# CAN-I2C.net
KiCad netlist of a schematic drawn in EAGLE
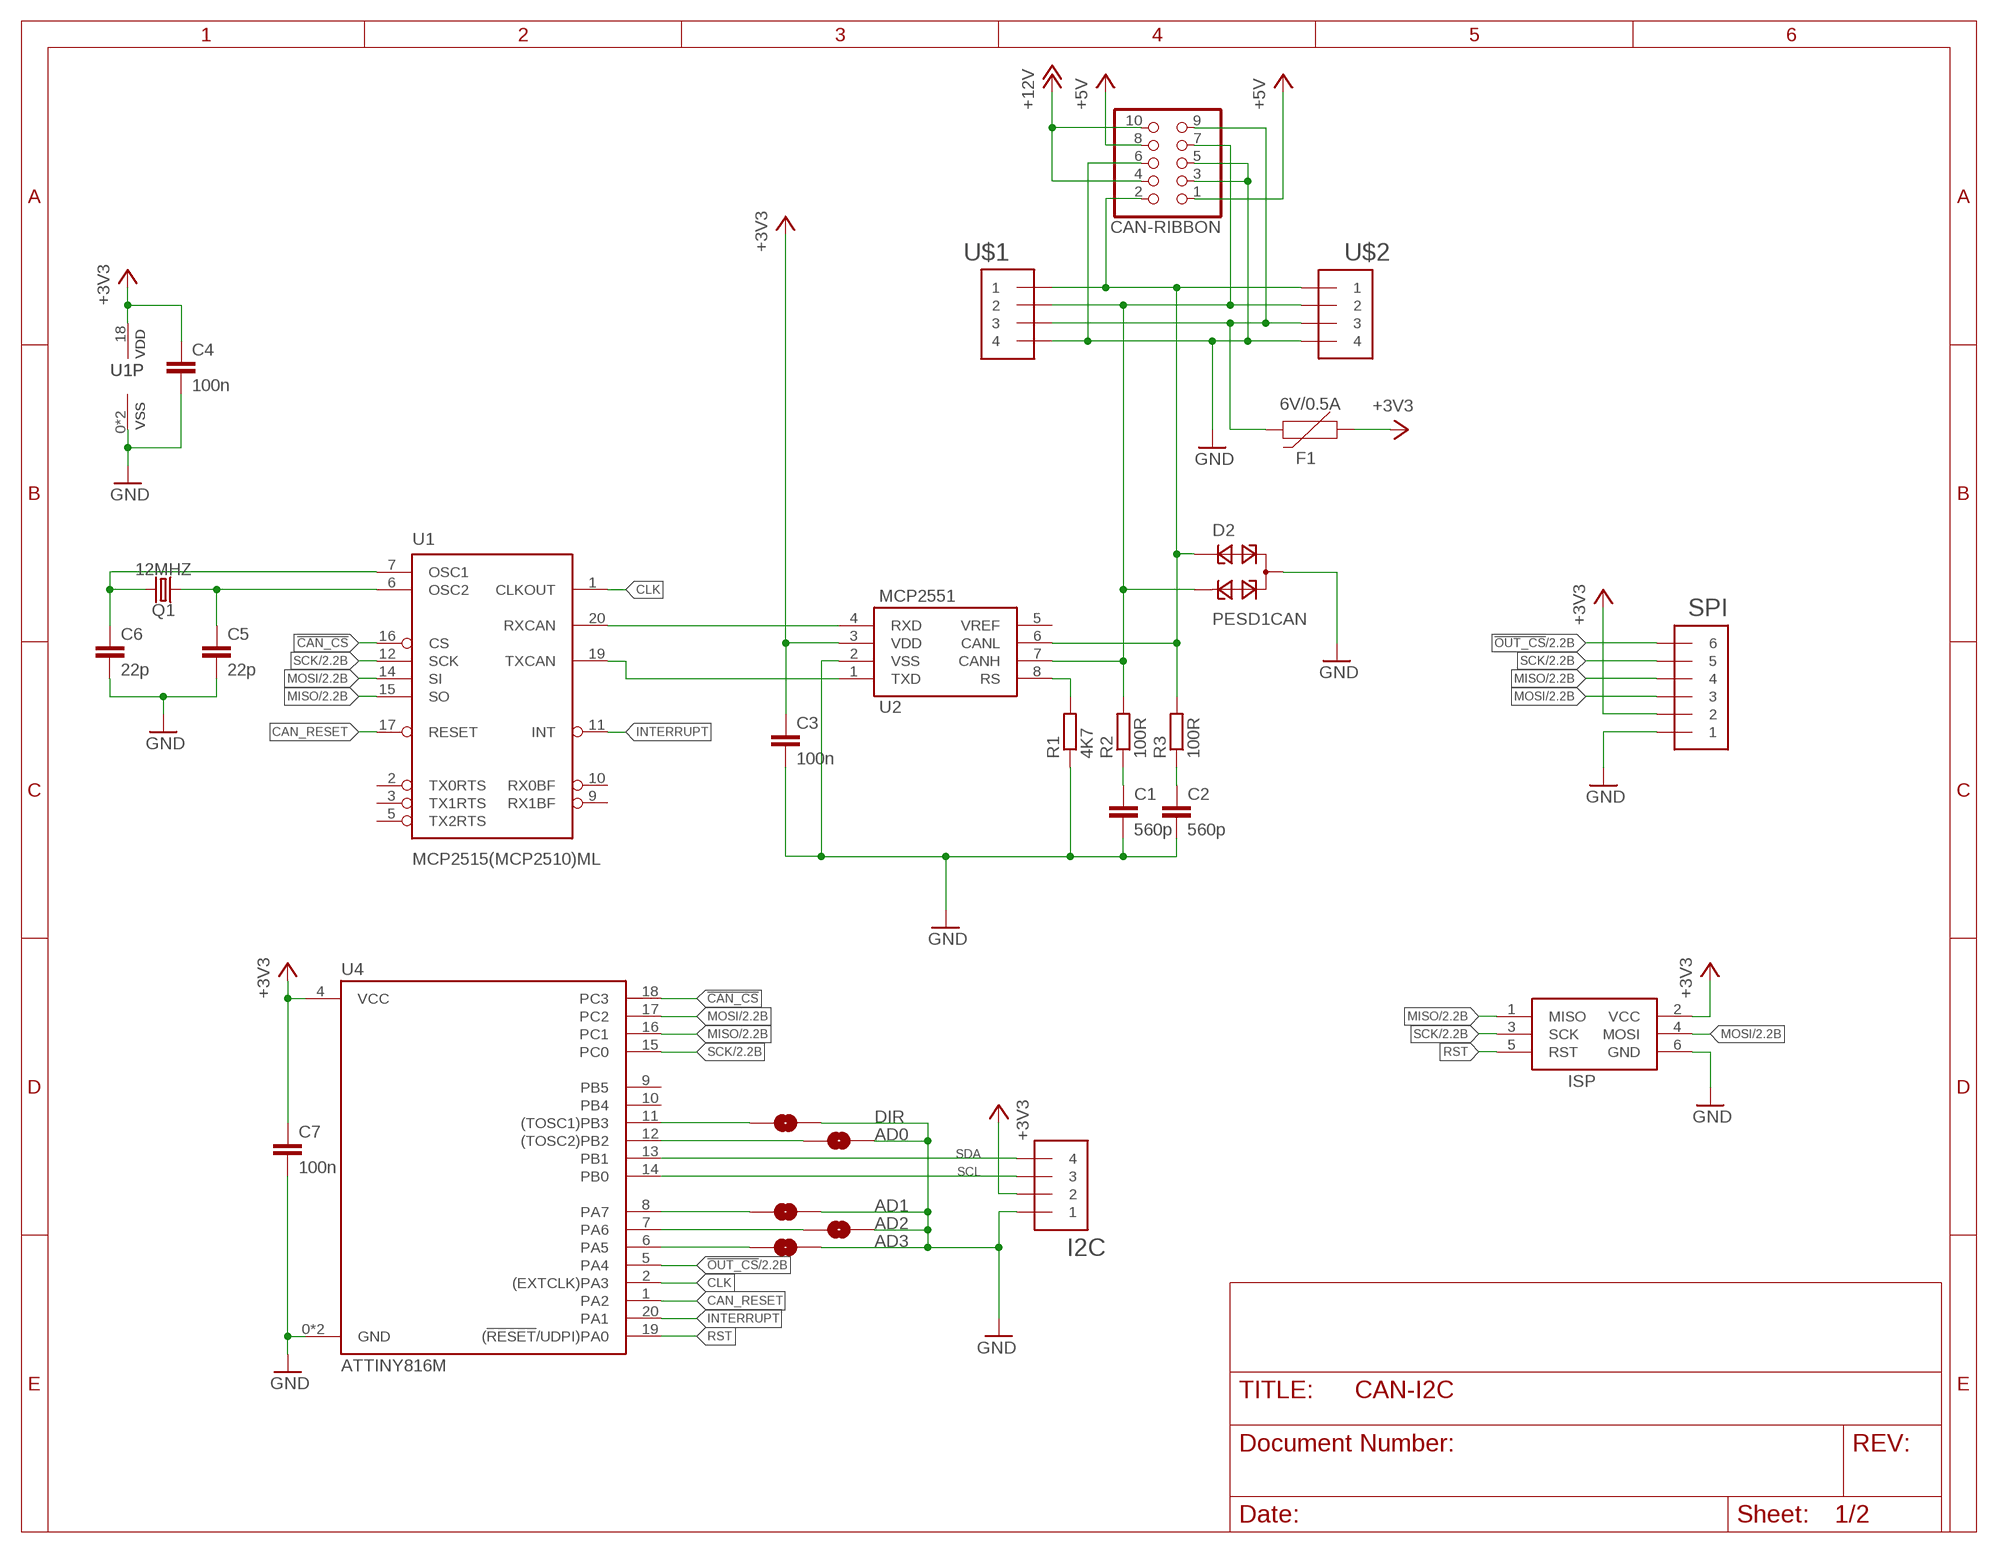
[diagram p0: schematic, sheet 1]
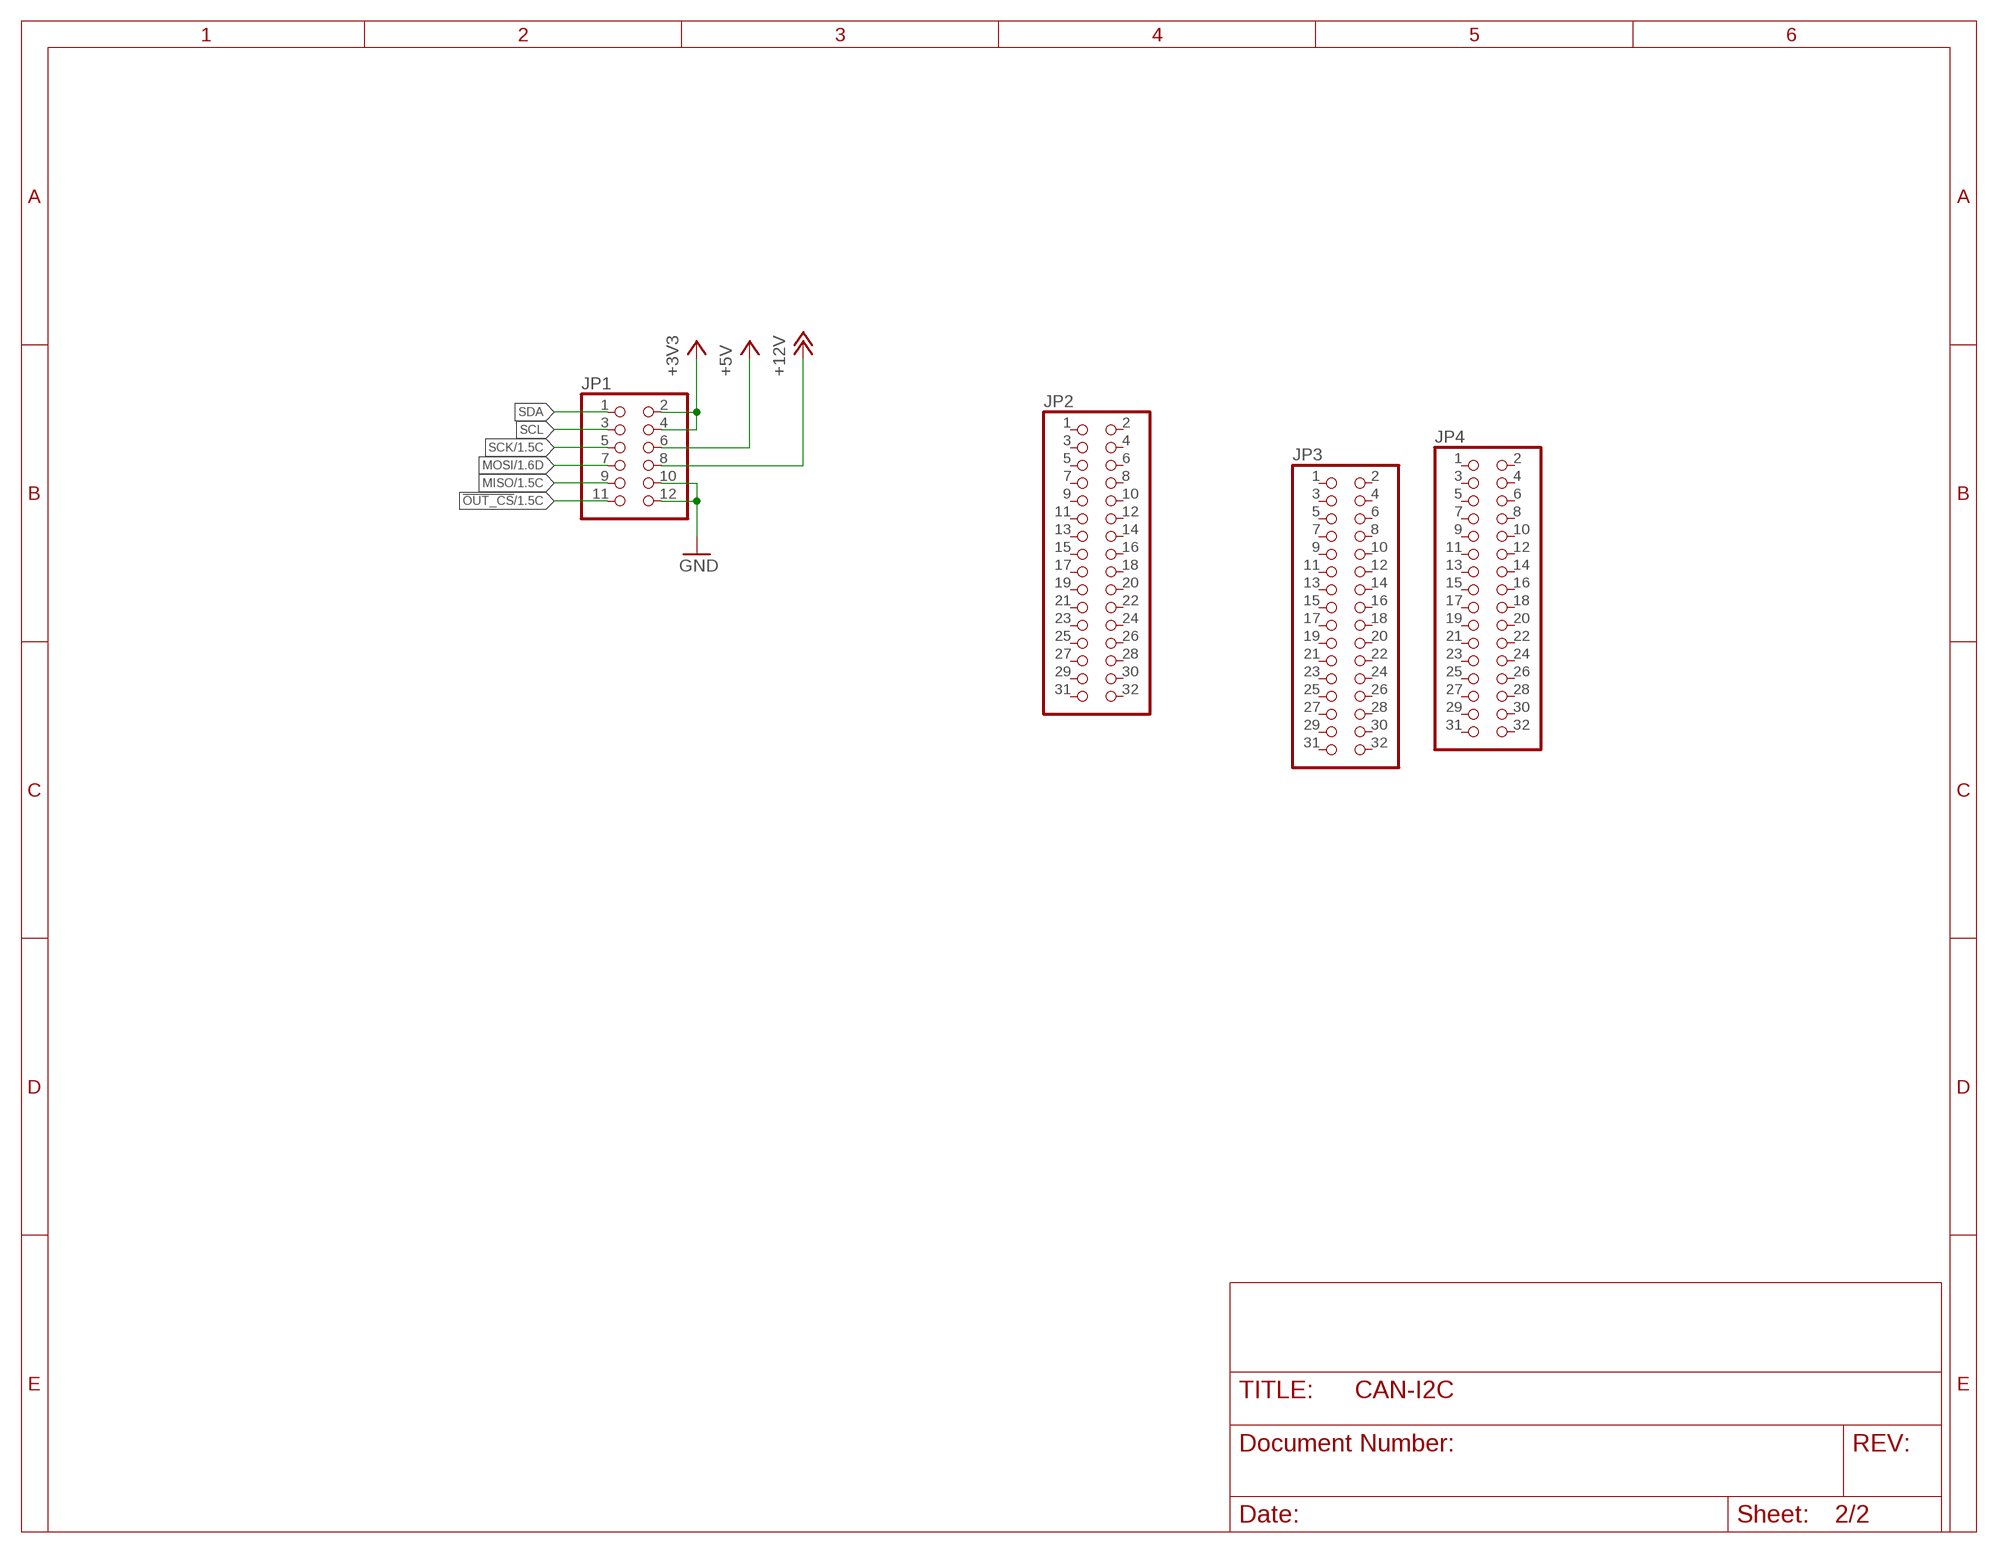
[diagram p1: schematic, sheet 2]

(export (version "E")
  (design (tool "Eeschema 10.0.6"))
  (components
    (comp (ref "JP1")
      (value "PINHD-2X6")
      (footprint "eagle-import:2X06")
      (libsource (lib "eagle-import") (part "PINHD-2X6"))
    )
    (comp (ref "JP2")
      (value "PINHD-2X16")
      (footprint "eagle-import:2X16")
      (libsource (lib "eagle-import") (part "PINHD-2X16"))
    )
    (comp (ref "JP3")
      (value "PINHD-2X16")
      (footprint "eagle-import:2X16")
      (libsource (lib "eagle-import") (part "PINHD-2X16"))
    )
    (comp (ref "JP4")
      (value "PINHD-2X16")
      (footprint "eagle-import:2X16")
      (libsource (lib "eagle-import") (part "PINHD-2X16"))
    )
    (comp (ref "AD0")
      (value "JUMPER-SMT_2_NO_SILK")
      (footprint "eagle-import:SMT-JUMPER_2_NO_SILK")
      (libsource (lib "eagle-import") (part "JUMPER-SMT_2_NO_SILK"))
    )
    (comp (ref "AD1")
      (value "JUMPER-SMT_2_NO_SILK")
      (footprint "eagle-import:SMT-JUMPER_2_NO_SILK")
      (libsource (lib "eagle-import") (part "JUMPER-SMT_2_NO_SILK"))
    )
    (comp (ref "AD2")
      (value "JUMPER-SMT_2_NO_SILK")
      (footprint "eagle-import:SMT-JUMPER_2_NO_SILK")
      (libsource (lib "eagle-import") (part "JUMPER-SMT_2_NO_SILK"))
    )
    (comp (ref "AD3")
      (value "JUMPER-SMT_2_NO_SILK")
      (footprint "eagle-import:SMT-JUMPER_2_NO_SILK")
      (libsource (lib "eagle-import") (part "JUMPER-SMT_2_NO_SILK"))
    )
    (comp (ref "C1")
      (value "560p")
      (footprint "eagle-import:C0603")
      (libsource (lib "eagle-import") (part "C-EUC0603"))
    )
    (comp (ref "C2")
      (value "560p")
      (footprint "eagle-import:C0603")
      (libsource (lib "eagle-import") (part "C-EUC0603"))
    )
    (comp (ref "C3")
      (value "100n")
      (footprint "eagle-import:C0603")
      (libsource (lib "eagle-import") (part "C-EUC0603"))
    )
    (comp (ref "C4")
      (value "100n")
      (footprint "eagle-import:C0603")
      (libsource (lib "eagle-import") (part "C-EUC0603"))
    )
    (comp (ref "C5")
      (value "22p")
      (footprint "eagle-import:C0603")
      (libsource (lib "eagle-import") (part "C-EUC0603"))
    )
    (comp (ref "C6")
      (value "22p")
      (footprint "eagle-import:C0603")
      (libsource (lib "eagle-import") (part "C-EUC0603"))
    )
    (comp (ref "C7")
      (value "100n")
      (footprint "eagle-import:C0603")
      (libsource (lib "eagle-import") (part "C-EUC0603"))
    )
    (comp (ref "CAN-RIBBON")
      (value "PINHD-2X5_2.54-SMD")
      (footprint "eagle-import:2X05SMD")
      (libsource (lib "eagle-import") (part "PINHD-2X5_2.54-SMD"))
    )
    (comp (ref "D2")
      (value "PESD1CAN")
      (footprint "eagle-import:SOT23")
      (libsource (lib "eagle-import") (part "PESD1CAN"))
    )
    (comp (ref "DIR")
      (value "JUMPER-SMT_2_NO_SILK")
      (footprint "eagle-import:SMT-JUMPER_2_NO_SILK")
      (libsource (lib "eagle-import") (part "JUMPER-SMT_2_NO_SILK"))
    )
    (comp (ref "F1")
      (value "6V/0.5A")
      (footprint "eagle-import:1206")
      (libsource (lib "eagle-import") (part "PPTC_HALF-AMP"))
    )
    (comp (ref "I2C")
      (value "STRAWSON_EAGLE_LIB_JST_SH_4")
      (footprint "eagle-import:STRAWSON_EAGLE_LIB_JST_SH_4_SMD")
      (libsource (lib "eagle-import") (part "STRAWSON_EAGLE_LIB_JST_SH_4"))
    )
    (comp (ref "ISP")
      (value "AVRISP-6")
      (footprint "eagle-import:AVRISP")
      (libsource (lib "eagle-import") (part "AVRISP-6"))
    )
    (comp (ref "Q1")
      (value "12MHZ")
      (footprint "eagle-import:CRYSTAL-SMD-3.2X1.5MM")
      (libsource (lib "eagle-import") (part "CRYSTALSMD-3.2X1.5"))
    )
    (comp (ref "R1")
      (value "4K7")
      (footprint "eagle-import:R0603")
      (libsource (lib "eagle-import") (part "R-EU_R0603"))
    )
    (comp (ref "R2")
      (value "100R")
      (footprint "eagle-import:R0603")
      (libsource (lib "eagle-import") (part "R-EU_R0603"))
    )
    (comp (ref "R3")
      (value "100R")
      (footprint "eagle-import:R0603")
      (libsource (lib "eagle-import") (part "R-EU_R0603"))
    )
    (comp (ref "SPI")
      (value "STRAWSON_EAGLE_LIB_JST_SH_6")
      (footprint "eagle-import:STRAWSON_EAGLE_LIB_JST_SH_6")
      (libsource (lib "eagle-import") (part "STRAWSON_EAGLE_LIB_JST_SH_6"))
    )
    (comp (ref "U$1")
      (value "STRAWSON_EAGLE_LIB_JST_SH_4")
      (footprint "eagle-import:STRAWSON_EAGLE_LIB_JST_SH_4_SMD")
      (libsource (lib "eagle-import") (part "STRAWSON_EAGLE_LIB_JST_SH_4"))
    )
    (comp (ref "U$2")
      (value "STRAWSON_EAGLE_LIB_JST_SH_4")
      (footprint "eagle-import:STRAWSON_EAGLE_LIB_JST_SH_4_SMD")
      (libsource (lib "eagle-import") (part "STRAWSON_EAGLE_LIB_JST_SH_4"))
    )
    (comp (ref "U1")
      (value "MCP2515(MCP2510)ML")
      (footprint "eagle-import:QFN20")
      (libsource (lib "eagle-import") (part "MCP2515(MCP2510)ML"))
    )
    (comp (ref "U2")
      (value "MCP2551")
      (footprint "eagle-import:SO08")
      (libsource (lib "eagle-import") (part "MCP2551"))
    )
    (comp (ref "U4")
      (value "ATTINY816M")
      (footprint "eagle-import:QFN20")
      (libsource (lib "eagle-import") (part "ATTINY816M"))
    )
  )
  (nets
    (net (code "1") (name "+3V3") (class "Default")
      (node (ref "C3") (pin "1") (pinfunction "1_1") (pintype "passive"))
      (node (ref "C4") (pin "1") (pinfunction "1_1") (pintype "passive"))
      (node (ref "C7") (pin "1") (pinfunction "1_1") (pintype "passive"))
      (node (ref "F1") (pin "1") (pinfunction "1_1") (pintype "bidirectional"))
      (node (ref "I2C") (pin "2") (pinfunction "2_2") (pintype "bidirectional"))
      (node (ref "ISP") (pin "2") (pinfunction "VCC_2") (pintype "power_in"))
      (node (ref "JP1") (pin "2") (pinfunction "2_2") (pintype "passive"))
      (node (ref "JP1") (pin "4") (pinfunction "4_4") (pintype "passive"))
      (node (ref "SPI") (pin "2") (pinfunction "2_2") (pintype "bidirectional"))
      (node (ref "U1") (pin "18") (pinfunction "VDD_18") (pintype "power_in"))
      (node (ref "U2") (pin "3") (pinfunction "VDD_3") (pintype "bidirectional"))
      (node (ref "U4") (pin "4") (pinfunction "VCC_4") (pintype "bidirectional"))
    )
    (net (code "2") (name "+5V") (class "Default")
      (node (ref "CAN-RIBBON") (pin "1") (pinfunction "1_1") (pintype "passive"))
      (node (ref "CAN-RIBBON") (pin "8") (pinfunction "8_8") (pintype "passive"))
      (node (ref "JP1") (pin "6") (pinfunction "6_6") (pintype "passive"))
    )
    (net (code "3") (name "+12V") (class "Default")
      (node (ref "CAN-RIBBON") (pin "10") (pinfunction "10_10") (pintype "passive"))
      (node (ref "CAN-RIBBON") (pin "4") (pinfunction "4_4") (pintype "passive"))
      (node (ref "JP1") (pin "8") (pinfunction "8_8") (pintype "passive"))
    )
    (net (code "4") (name "CAN_RESET") (class "Default")
      (node (ref "U1") (pin "17") (pinfunction "RESET_17") (pintype "input"))
      (node (ref "U4") (pin "1") (pinfunction "PA2_1") (pintype "bidirectional"))
    )
    (net (code "5") (name "CLK") (class "Default")
      (node (ref "U1") (pin "1") (pinfunction "CLKOUT_1") (pintype "output"))
      (node (ref "U4") (pin "2") (pinfunction "(EXTCLK)PA3_2") (pintype "bidirectional"))
    )
    (net (code "6") (name "GND") (class "Default")
      (node (ref "AD0") (pin "2") (pinfunction "2_2") (pintype "passive"))
      (node (ref "AD1") (pin "2") (pinfunction "2_2") (pintype "passive"))
      (node (ref "AD2") (pin "2") (pinfunction "2_2") (pintype "passive"))
      (node (ref "AD3") (pin "2") (pinfunction "2_2") (pintype "passive"))
      (node (ref "C1") (pin "2") (pinfunction "2_2") (pintype "passive"))
      (node (ref "C2") (pin "2") (pinfunction "2_2") (pintype "passive"))
      (node (ref "C3") (pin "2") (pinfunction "2_2") (pintype "passive"))
      (node (ref "C4") (pin "2") (pinfunction "2_2") (pintype "passive"))
      (node (ref "C5") (pin "2") (pinfunction "2_2") (pintype "passive"))
      (node (ref "C6") (pin "2") (pinfunction "2_2") (pintype "passive"))
      (node (ref "C7") (pin "2") (pinfunction "2_2") (pintype "passive"))
      (node (ref "CAN-RIBBON") (pin "3") (pinfunction "3_3") (pintype "passive"))
      (node (ref "CAN-RIBBON") (pin "5") (pinfunction "5_5") (pintype "passive"))
      (node (ref "CAN-RIBBON") (pin "6") (pinfunction "6_6") (pintype "passive"))
      (node (ref "D2") (pin "3") (pinfunction "3_3") (pintype "passive"))
      (node (ref "DIR") (pin "2") (pinfunction "2_2") (pintype "passive"))
      (node (ref "I2C") (pin "1") (pinfunction "1_1") (pintype "bidirectional"))
      (node (ref "ISP") (pin "6") (pinfunction "GND_6") (pintype "power_in"))
      (node (ref "JP1") (pin "10") (pinfunction "10_10") (pintype "passive"))
      (node (ref "JP1") (pin "12") (pinfunction "12_12") (pintype "passive"))
      (node (ref "R1") (pin "1") (pinfunction "1_1") (pintype "passive"))
      (node (ref "SPI") (pin "1") (pinfunction "1_1") (pintype "bidirectional"))
      (node (ref "U$1") (pin "4") (pinfunction "4_4") (pintype "bidirectional"))
      (node (ref "U$2") (pin "4") (pinfunction "4_4") (pintype "bidirectional"))
      (node (ref "U1") (pin "0") (pinfunction "VSS_0") (pintype "power_in"))
      (node (ref "U1") (pin "8") (pinfunction "VSS_8") (pintype "power_in"))
      (node (ref "U2") (pin "2") (pinfunction "VSS_2") (pintype "bidirectional"))
      (node (ref "U4") (pin "0") (pinfunction "GND_0") (pintype "bidirectional"))
      (node (ref "U4") (pin "3") (pinfunction "GND_3") (pintype "bidirectional"))
    )
    (net (code "7") (name "INTERRUPT") (class "Default")
      (node (ref "U1") (pin "11") (pinfunction "INT_11") (pintype "output"))
      (node (ref "U4") (pin "20") (pinfunction "PA1_20") (pintype "bidirectional"))
    )
    (net (code "8") (name "MISO") (class "Default")
      (node (ref "ISP") (pin "1") (pinfunction "MISO_1") (pintype "input"))
      (node (ref "JP1") (pin "9") (pinfunction "9_9") (pintype "passive"))
      (node (ref "SPI") (pin "4") (pinfunction "4_4") (pintype "bidirectional"))
      (node (ref "U1") (pin "15") (pinfunction "SO_15") (pintype "output"))
      (node (ref "U4") (pin "16") (pinfunction "PC1_16") (pintype "bidirectional"))
    )
    (net (code "9") (name "MOSI") (class "Default")
      (node (ref "ISP") (pin "4") (pinfunction "MOSI_4") (pintype "output"))
      (node (ref "JP1") (pin "7") (pinfunction "7_7") (pintype "passive"))
      (node (ref "SPI") (pin "3") (pinfunction "3_3") (pintype "bidirectional"))
      (node (ref "U1") (pin "14") (pinfunction "SI_14") (pintype "input"))
      (node (ref "U4") (pin "17") (pinfunction "PC2_17") (pintype "bidirectional"))
    )
    (net (code "10") (name "Net-(C1-Pad1)") (class "Default")
      (node (ref "C1") (pin "1") (pinfunction "1_1") (pintype "passive"))
      (node (ref "R2") (pin "1") (pinfunction "1_1") (pintype "passive"))
    )
    (net (code "11") (name "Net-(C2-Pad1)") (class "Default")
      (node (ref "C2") (pin "1") (pinfunction "1_1") (pintype "passive"))
      (node (ref "R3") (pin "1") (pinfunction "1_1") (pintype "passive"))
    )
    (net (code "12") (name "Net-(CAN-RIBBON-Pad9)") (class "Default")
      (node (ref "CAN-RIBBON") (pin "9") (pinfunction "9_9") (pintype "passive"))
      (node (ref "F1") (pin "2") (pinfunction "2_2") (pintype "bidirectional"))
      (node (ref "U$1") (pin "3") (pinfunction "3_3") (pintype "bidirectional"))
      (node (ref "U$2") (pin "3") (pinfunction "3_3") (pintype "bidirectional"))
    )
    (net (code "13") (name "Net-(Q1-1)") (class "Default")
      (node (ref "C5") (pin "1") (pinfunction "1_1") (pintype "passive"))
      (node (ref "Q1") (pin "P$1") (pinfunction "1_P$1") (pintype "passive"))
      (node (ref "U1") (pin "6") (pinfunction "OSC2_6") (pintype "output"))
    )
    (net (code "14") (name "Net-(Q1-2)") (class "Default")
      (node (ref "C6") (pin "1") (pinfunction "1_1") (pintype "passive"))
      (node (ref "Q1") (pin "P$2") (pinfunction "2_P$2") (pintype "passive"))
      (node (ref "U1") (pin "7") (pinfunction "OSC1_7") (pintype "input"))
    )
    (net (code "15") (name "Net-(U1A-RXCAN)") (class "Default")
      (node (ref "U1") (pin "20") (pinfunction "RXCAN_20") (pintype "input"))
      (node (ref "U2") (pin "4") (pinfunction "RXD_4") (pintype "bidirectional"))
    )
    (net (code "16") (name "Net-(U1A-TXCAN)") (class "Default")
      (node (ref "U1") (pin "19") (pinfunction "TXCAN_19") (pintype "output"))
      (node (ref "U2") (pin "1") (pinfunction "TXD_1") (pintype "bidirectional"))
    )
    (net (code "17") (name "Net-(U2-CANH)") (class "Default")
      (node (ref "CAN-RIBBON") (pin "7") (pinfunction "7_7") (pintype "passive"))
      (node (ref "D2") (pin "2") (pinfunction "2_2") (pintype "passive"))
      (node (ref "R2") (pin "2") (pinfunction "2_2") (pintype "passive"))
      (node (ref "U$1") (pin "2") (pinfunction "2_2") (pintype "bidirectional"))
      (node (ref "U$2") (pin "2") (pinfunction "2_2") (pintype "bidirectional"))
      (node (ref "U2") (pin "7") (pinfunction "CANH_7") (pintype "bidirectional"))
    )
    (net (code "18") (name "Net-(U2-CANL)") (class "Default")
      (node (ref "CAN-RIBBON") (pin "2") (pinfunction "2_2") (pintype "passive"))
      (node (ref "D2") (pin "1") (pinfunction "1_1") (pintype "passive"))
      (node (ref "R3") (pin "2") (pinfunction "2_2") (pintype "passive"))
      (node (ref "U$1") (pin "1") (pinfunction "1_1") (pintype "bidirectional"))
      (node (ref "U$2") (pin "1") (pinfunction "1_1") (pintype "bidirectional"))
      (node (ref "U2") (pin "6") (pinfunction "CANL_6") (pintype "bidirectional"))
    )
    (net (code "19") (name "Net-(U2-RS)") (class "Default")
      (node (ref "R1") (pin "2") (pinfunction "2_2") (pintype "passive"))
      (node (ref "U2") (pin "8") (pinfunction "RS_8") (pintype "bidirectional"))
    )
    (net (code "20") (name "Net-(U4-(TOSC1)PB3)") (class "Default")
      (node (ref "DIR") (pin "1") (pinfunction "1_1") (pintype "passive"))
      (node (ref "U4") (pin "11") (pinfunction "(TOSC1)PB3_11") (pintype "bidirectional"))
    )
    (net (code "21") (name "Net-(U4-(TOSC2)PB2)") (class "Default")
      (node (ref "AD0") (pin "1") (pinfunction "1_1") (pintype "passive"))
      (node (ref "U4") (pin "12") (pinfunction "(TOSC2)PB2_12") (pintype "bidirectional"))
    )
    (net (code "22") (name "Net-(U4-PA5)") (class "Default")
      (node (ref "AD3") (pin "1") (pinfunction "1_1") (pintype "passive"))
      (node (ref "U4") (pin "6") (pinfunction "PA5_6") (pintype "bidirectional"))
    )
    (net (code "23") (name "Net-(U4-PA6)") (class "Default")
      (node (ref "AD2") (pin "1") (pinfunction "1_1") (pintype "passive"))
      (node (ref "U4") (pin "7") (pinfunction "PA6_7") (pintype "bidirectional"))
    )
    (net (code "24") (name "Net-(U4-PA7)") (class "Default")
      (node (ref "AD1") (pin "1") (pinfunction "1_1") (pintype "passive"))
      (node (ref "U4") (pin "8") (pinfunction "PA7_8") (pintype "bidirectional"))
    )
    (net (code "25") (name "RST") (class "Default")
      (node (ref "ISP") (pin "5") (pinfunction "RST_5") (pintype "output"))
      (node (ref "U4") (pin "19") (pinfunction "(~{RESET}/UDPI)PA0_19") (pintype "bidirectional"))
    )
    (net (code "26") (name "SCK") (class "Default")
      (node (ref "ISP") (pin "3") (pinfunction "SCK_3") (pintype "output"))
      (node (ref "JP1") (pin "5") (pinfunction "5_5") (pintype "passive"))
      (node (ref "SPI") (pin "5") (pinfunction "5_5") (pintype "bidirectional"))
      (node (ref "U1") (pin "12") (pinfunction "SCK_12") (pintype "input"))
      (node (ref "U4") (pin "15") (pinfunction "PC0_15") (pintype "bidirectional"))
    )
    (net (code "27") (name "SCL") (class "Default")
      (node (ref "I2C") (pin "3") (pinfunction "3_3") (pintype "bidirectional"))
      (node (ref "JP1") (pin "3") (pinfunction "3_3") (pintype "passive"))
      (node (ref "U4") (pin "14") (pinfunction "PB0_14") (pintype "bidirectional"))
    )
    (net (code "28") (name "SDA") (class "Default")
      (node (ref "I2C") (pin "4") (pinfunction "4_4") (pintype "bidirectional"))
      (node (ref "JP1") (pin "1") (pinfunction "1_1") (pintype "passive"))
      (node (ref "U4") (pin "13") (pinfunction "PB1_13") (pintype "bidirectional"))
    )
    (net (code "29") (name "unconnected-(JP2-Pad1)") (class "Default")
      (node (ref "JP2") (pin "1") (pinfunction "1_1") (pintype "passive"))
    )
    (net (code "30") (name "unconnected-(JP2-Pad2)") (class "Default")
      (node (ref "JP2") (pin "2") (pinfunction "2_2") (pintype "passive"))
    )
    (net (code "31") (name "unconnected-(JP2-Pad3)") (class "Default")
      (node (ref "JP2") (pin "3") (pinfunction "3_3") (pintype "passive"))
    )
    (net (code "32") (name "unconnected-(JP2-Pad4)") (class "Default")
      (node (ref "JP2") (pin "4") (pinfunction "4_4") (pintype "passive"))
    )
    (net (code "33") (name "unconnected-(JP2-Pad5)") (class "Default")
      (node (ref "JP2") (pin "5") (pinfunction "5_5") (pintype "passive"))
    )
    (net (code "34") (name "unconnected-(JP2-Pad6)") (class "Default")
      (node (ref "JP2") (pin "6") (pinfunction "6_6") (pintype "passive"))
    )
    (net (code "35") (name "unconnected-(JP2-Pad7)") (class "Default")
      (node (ref "JP2") (pin "7") (pinfunction "7_7") (pintype "passive"))
    )
    (net (code "36") (name "unconnected-(JP2-Pad8)") (class "Default")
      (node (ref "JP2") (pin "8") (pinfunction "8_8") (pintype "passive"))
    )
    (net (code "37") (name "unconnected-(JP2-Pad9)") (class "Default")
      (node (ref "JP2") (pin "9") (pinfunction "9_9") (pintype "passive"))
    )
    (net (code "38") (name "unconnected-(JP2-Pad10)") (class "Default")
      (node (ref "JP2") (pin "10") (pinfunction "10_10") (pintype "passive"))
    )
    (net (code "39") (name "unconnected-(JP2-Pad11)") (class "Default")
      (node (ref "JP2") (pin "11") (pinfunction "11_11") (pintype "passive"))
    )
    (net (code "40") (name "unconnected-(JP2-Pad12)") (class "Default")
      (node (ref "JP2") (pin "12") (pinfunction "12_12") (pintype "passive"))
    )
    (net (code "41") (name "unconnected-(JP2-Pad13)") (class "Default")
      (node (ref "JP2") (pin "13") (pinfunction "13_13") (pintype "passive"))
    )
    (net (code "42") (name "unconnected-(JP2-Pad14)") (class "Default")
      (node (ref "JP2") (pin "14") (pinfunction "14_14") (pintype "passive"))
    )
    (net (code "43") (name "unconnected-(JP2-Pad15)") (class "Default")
      (node (ref "JP2") (pin "15") (pinfunction "15_15") (pintype "passive"))
    )
    (net (code "44") (name "unconnected-(JP2-Pad16)") (class "Default")
      (node (ref "JP2") (pin "16") (pinfunction "16_16") (pintype "passive"))
    )
    (net (code "45") (name "unconnected-(JP2-Pad17)") (class "Default")
      (node (ref "JP2") (pin "17") (pinfunction "17_17") (pintype "passive"))
    )
    (net (code "46") (name "unconnected-(JP2-Pad18)") (class "Default")
      (node (ref "JP2") (pin "18") (pinfunction "18_18") (pintype "passive"))
    )
    (net (code "47") (name "unconnected-(JP2-Pad19)") (class "Default")
      (node (ref "JP2") (pin "19") (pinfunction "19_19") (pintype "passive"))
    )
    (net (code "48") (name "unconnected-(JP2-Pad20)") (class "Default")
      (node (ref "JP2") (pin "20") (pinfunction "20_20") (pintype "passive"))
    )
    (net (code "49") (name "unconnected-(JP2-Pad21)") (class "Default")
      (node (ref "JP2") (pin "21") (pinfunction "21_21") (pintype "passive"))
    )
    (net (code "50") (name "unconnected-(JP2-Pad22)") (class "Default")
      (node (ref "JP2") (pin "22") (pinfunction "22_22") (pintype "passive"))
    )
    (net (code "51") (name "unconnected-(JP2-Pad23)") (class "Default")
      (node (ref "JP2") (pin "23") (pinfunction "23_23") (pintype "passive"))
    )
    (net (code "52") (name "unconnected-(JP2-Pad24)") (class "Default")
      (node (ref "JP2") (pin "24") (pinfunction "24_24") (pintype "passive"))
    )
    (net (code "53") (name "unconnected-(JP2-Pad25)") (class "Default")
      (node (ref "JP2") (pin "25") (pinfunction "25_25") (pintype "passive"))
    )
    (net (code "54") (name "unconnected-(JP2-Pad26)") (class "Default")
      (node (ref "JP2") (pin "26") (pinfunction "26_26") (pintype "passive"))
    )
    (net (code "55") (name "unconnected-(JP2-Pad27)") (class "Default")
      (node (ref "JP2") (pin "27") (pinfunction "27_27") (pintype "passive"))
    )
    (net (code "56") (name "unconnected-(JP2-Pad28)") (class "Default")
      (node (ref "JP2") (pin "28") (pinfunction "28_28") (pintype "passive"))
    )
    (net (code "57") (name "unconnected-(JP2-Pad29)") (class "Default")
      (node (ref "JP2") (pin "29") (pinfunction "29_29") (pintype "passive"))
    )
    (net (code "58") (name "unconnected-(JP2-Pad30)") (class "Default")
      (node (ref "JP2") (pin "30") (pinfunction "30_30") (pintype "passive"))
    )
    (net (code "59") (name "unconnected-(JP2-Pad31)") (class "Default")
      (node (ref "JP2") (pin "31") (pinfunction "31_31") (pintype "passive"))
    )
    (net (code "60") (name "unconnected-(JP2-Pad32)") (class "Default")
      (node (ref "JP2") (pin "32") (pinfunction "32_32") (pintype "passive"))
    )
    (net (code "61") (name "unconnected-(JP3-Pad1)") (class "Default")
      (node (ref "JP3") (pin "1") (pinfunction "1_1") (pintype "passive"))
    )
    (net (code "62") (name "unconnected-(JP3-Pad2)") (class "Default")
      (node (ref "JP3") (pin "2") (pinfunction "2_2") (pintype "passive"))
    )
    (net (code "63") (name "unconnected-(JP3-Pad3)") (class "Default")
      (node (ref "JP3") (pin "3") (pinfunction "3_3") (pintype "passive"))
    )
    (net (code "64") (name "unconnected-(JP3-Pad4)") (class "Default")
      (node (ref "JP3") (pin "4") (pinfunction "4_4") (pintype "passive"))
    )
    (net (code "65") (name "unconnected-(JP3-Pad5)") (class "Default")
      (node (ref "JP3") (pin "5") (pinfunction "5_5") (pintype "passive"))
    )
    (net (code "66") (name "unconnected-(JP3-Pad6)") (class "Default")
      (node (ref "JP3") (pin "6") (pinfunction "6_6") (pintype "passive"))
    )
    (net (code "67") (name "unconnected-(JP3-Pad7)") (class "Default")
      (node (ref "JP3") (pin "7") (pinfunction "7_7") (pintype "passive"))
    )
    (net (code "68") (name "unconnected-(JP3-Pad8)") (class "Default")
      (node (ref "JP3") (pin "8") (pinfunction "8_8") (pintype "passive"))
    )
    (net (code "69") (name "unconnected-(JP3-Pad9)") (class "Default")
      (node (ref "JP3") (pin "9") (pinfunction "9_9") (pintype "passive"))
    )
    (net (code "70") (name "unconnected-(JP3-Pad10)") (class "Default")
      (node (ref "JP3") (pin "10") (pinfunction "10_10") (pintype "passive"))
    )
    (net (code "71") (name "unconnected-(JP3-Pad11)") (class "Default")
      (node (ref "JP3") (pin "11") (pinfunction "11_11") (pintype "passive"))
    )
    (net (code "72") (name "unconnected-(JP3-Pad12)") (class "Default")
      (node (ref "JP3") (pin "12") (pinfunction "12_12") (pintype "passive"))
    )
    (net (code "73") (name "unconnected-(JP3-Pad13)") (class "Default")
      (node (ref "JP3") (pin "13") (pinfunction "13_13") (pintype "passive"))
    )
    (net (code "74") (name "unconnected-(JP3-Pad14)") (class "Default")
      (node (ref "JP3") (pin "14") (pinfunction "14_14") (pintype "passive"))
    )
    (net (code "75") (name "unconnected-(JP3-Pad15)") (class "Default")
      (node (ref "JP3") (pin "15") (pinfunction "15_15") (pintype "passive"))
    )
    (net (code "76") (name "unconnected-(JP3-Pad16)") (class "Default")
      (node (ref "JP3") (pin "16") (pinfunction "16_16") (pintype "passive"))
    )
    (net (code "77") (name "unconnected-(JP3-Pad17)") (class "Default")
      (node (ref "JP3") (pin "17") (pinfunction "17_17") (pintype "passive"))
    )
    (net (code "78") (name "unconnected-(JP3-Pad18)") (class "Default")
      (node (ref "JP3") (pin "18") (pinfunction "18_18") (pintype "passive"))
    )
    (net (code "79") (name "unconnected-(JP3-Pad19)") (class "Default")
      (node (ref "JP3") (pin "19") (pinfunction "19_19") (pintype "passive"))
    )
    (net (code "80") (name "unconnected-(JP3-Pad20)") (class "Default")
      (node (ref "JP3") (pin "20") (pinfunction "20_20") (pintype "passive"))
    )
    (net (code "81") (name "unconnected-(JP3-Pad21)") (class "Default")
      (node (ref "JP3") (pin "21") (pinfunction "21_21") (pintype "passive"))
    )
    (net (code "82") (name "unconnected-(JP3-Pad22)") (class "Default")
      (node (ref "JP3") (pin "22") (pinfunction "22_22") (pintype "passive"))
    )
    (net (code "83") (name "unconnected-(JP3-Pad23)") (class "Default")
      (node (ref "JP3") (pin "23") (pinfunction "23_23") (pintype "passive"))
    )
    (net (code "84") (name "unconnected-(JP3-Pad24)") (class "Default")
      (node (ref "JP3") (pin "24") (pinfunction "24_24") (pintype "passive"))
    )
    (net (code "85") (name "unconnected-(JP3-Pad25)") (class "Default")
      (node (ref "JP3") (pin "25") (pinfunction "25_25") (pintype "passive"))
    )
    (net (code "86") (name "unconnected-(JP3-Pad26)") (class "Default")
      (node (ref "JP3") (pin "26") (pinfunction "26_26") (pintype "passive"))
    )
    (net (code "87") (name "unconnected-(JP3-Pad27)") (class "Default")
      (node (ref "JP3") (pin "27") (pinfunction "27_27") (pintype "passive"))
    )
    (net (code "88") (name "unconnected-(JP3-Pad28)") (class "Default")
      (node (ref "JP3") (pin "28") (pinfunction "28_28") (pintype "passive"))
    )
    (net (code "89") (name "unconnected-(JP3-Pad29)") (class "Default")
      (node (ref "JP3") (pin "29") (pinfunction "29_29") (pintype "passive"))
    )
    (net (code "90") (name "unconnected-(JP3-Pad30)") (class "Default")
      (node (ref "JP3") (pin "30") (pinfunction "30_30") (pintype "passive"))
    )
    (net (code "91") (name "unconnected-(JP3-Pad31)") (class "Default")
      (node (ref "JP3") (pin "31") (pinfunction "31_31") (pintype "passive"))
    )
    (net (code "92") (name "unconnected-(JP3-Pad32)") (class "Default")
      (node (ref "JP3") (pin "32") (pinfunction "32_32") (pintype "passive"))
    )
    (net (code "93") (name "unconnected-(JP4-Pad1)") (class "Default")
      (node (ref "JP4") (pin "1") (pinfunction "1_1") (pintype "passive"))
    )
    (net (code "94") (name "unconnected-(JP4-Pad2)") (class "Default")
      (node (ref "JP4") (pin "2") (pinfunction "2_2") (pintype "passive"))
    )
    (net (code "95") (name "unconnected-(JP4-Pad3)") (class "Default")
      (node (ref "JP4") (pin "3") (pinfunction "3_3") (pintype "passive"))
    )
    (net (code "96") (name "unconnected-(JP4-Pad4)") (class "Default")
      (node (ref "JP4") (pin "4") (pinfunction "4_4") (pintype "passive"))
    )
    (net (code "97") (name "unconnected-(JP4-Pad5)") (class "Default")
      (node (ref "JP4") (pin "5") (pinfunction "5_5") (pintype "passive"))
    )
    (net (code "98") (name "unconnected-(JP4-Pad6)") (class "Default")
      (node (ref "JP4") (pin "6") (pinfunction "6_6") (pintype "passive"))
    )
    (net (code "99") (name "unconnected-(JP4-Pad7)") (class "Default")
      (node (ref "JP4") (pin "7") (pinfunction "7_7") (pintype "passive"))
    )
    (net (code "100") (name "unconnected-(JP4-Pad8)") (class "Default")
      (node (ref "JP4") (pin "8") (pinfunction "8_8") (pintype "passive"))
    )
    (net (code "101") (name "unconnected-(JP4-Pad9)") (class "Default")
      (node (ref "JP4") (pin "9") (pinfunction "9_9") (pintype "passive"))
    )
    (net (code "102") (name "unconnected-(JP4-Pad10)") (class "Default")
      (node (ref "JP4") (pin "10") (pinfunction "10_10") (pintype "passive"))
    )
    (net (code "103") (name "unconnected-(JP4-Pad11)") (class "Default")
      (node (ref "JP4") (pin "11") (pinfunction "11_11") (pintype "passive"))
    )
    (net (code "104") (name "unconnected-(JP4-Pad12)") (class "Default")
      (node (ref "JP4") (pin "12") (pinfunction "12_12") (pintype "passive"))
    )
    (net (code "105") (name "unconnected-(JP4-Pad13)") (class "Default")
      (node (ref "JP4") (pin "13") (pinfunction "13_13") (pintype "passive"))
    )
    (net (code "106") (name "unconnected-(JP4-Pad14)") (class "Default")
      (node (ref "JP4") (pin "14") (pinfunction "14_14") (pintype "passive"))
    )
    (net (code "107") (name "unconnected-(JP4-Pad15)") (class "Default")
      (node (ref "JP4") (pin "15") (pinfunction "15_15") (pintype "passive"))
    )
    (net (code "108") (name "unconnected-(JP4-Pad16)") (class "Default")
      (node (ref "JP4") (pin "16") (pinfunction "16_16") (pintype "passive"))
    )
    (net (code "109") (name "unconnected-(JP4-Pad17)") (class "Default")
      (node (ref "JP4") (pin "17") (pinfunction "17_17") (pintype "passive"))
    )
    (net (code "110") (name "unconnected-(JP4-Pad18)") (class "Default")
      (node (ref "JP4") (pin "18") (pinfunction "18_18") (pintype "passive"))
    )
    (net (code "111") (name "unconnected-(JP4-Pad19)") (class "Default")
      (node (ref "JP4") (pin "19") (pinfunction "19_19") (pintype "passive"))
    )
    (net (code "112") (name "unconnected-(JP4-Pad20)") (class "Default")
      (node (ref "JP4") (pin "20") (pinfunction "20_20") (pintype "passive"))
    )
    (net (code "113") (name "unconnected-(JP4-Pad21)") (class "Default")
      (node (ref "JP4") (pin "21") (pinfunction "21_21") (pintype "passive"))
    )
    (net (code "114") (name "unconnected-(JP4-Pad22)") (class "Default")
      (node (ref "JP4") (pin "22") (pinfunction "22_22") (pintype "passive"))
    )
    (net (code "115") (name "unconnected-(JP4-Pad23)") (class "Default")
      (node (ref "JP4") (pin "23") (pinfunction "23_23") (pintype "passive"))
    )
    (net (code "116") (name "unconnected-(JP4-Pad24)") (class "Default")
      (node (ref "JP4") (pin "24") (pinfunction "24_24") (pintype "passive"))
    )
    (net (code "117") (name "unconnected-(JP4-Pad25)") (class "Default")
      (node (ref "JP4") (pin "25") (pinfunction "25_25") (pintype "passive"))
    )
    (net (code "118") (name "unconnected-(JP4-Pad26)") (class "Default")
      (node (ref "JP4") (pin "26") (pinfunction "26_26") (pintype "passive"))
    )
    (net (code "119") (name "unconnected-(JP4-Pad27)") (class "Default")
      (node (ref "JP4") (pin "27") (pinfunction "27_27") (pintype "passive"))
    )
    (net (code "120") (name "unconnected-(JP4-Pad28)") (class "Default")
      (node (ref "JP4") (pin "28") (pinfunction "28_28") (pintype "passive"))
    )
    (net (code "121") (name "unconnected-(JP4-Pad29)") (class "Default")
      (node (ref "JP4") (pin "29") (pinfunction "29_29") (pintype "passive"))
    )
    (net (code "122") (name "unconnected-(JP4-Pad30)") (class "Default")
      (node (ref "JP4") (pin "30") (pinfunction "30_30") (pintype "passive"))
    )
    (net (code "123") (name "unconnected-(JP4-Pad31)") (class "Default")
      (node (ref "JP4") (pin "31") (pinfunction "31_31") (pintype "passive"))
    )
    (net (code "124") (name "unconnected-(JP4-Pad32)") (class "Default")
      (node (ref "JP4") (pin "32") (pinfunction "32_32") (pintype "passive"))
    )
    (net (code "125") (name "unconnected-(U1A-RX0BF-Pad10)") (class "Default")
      (node (ref "U1") (pin "10") (pinfunction "RX0BF_10") (pintype "output"))
    )
    (net (code "126") (name "unconnected-(U1A-RX1BF-Pad9)") (class "Default")
      (node (ref "U1") (pin "9") (pinfunction "RX1BF_9") (pintype "output"))
    )
    (net (code "127") (name "unconnected-(U1A-TX0RTS-Pad2)") (class "Default")
      (node (ref "U1") (pin "2") (pinfunction "TX0RTS_2") (pintype "input"))
    )
    (net (code "128") (name "unconnected-(U1A-TX1RTS-Pad3)") (class "Default")
      (node (ref "U1") (pin "3") (pinfunction "TX1RTS_3") (pintype "input"))
    )
    (net (code "129") (name "unconnected-(U1A-TX2RTS-Pad5)") (class "Default")
      (node (ref "U1") (pin "5") (pinfunction "TX2RTS_5") (pintype "input"))
    )
    (net (code "130") (name "unconnected-(U2-VREF-Pad5)") (class "Default")
      (node (ref "U2") (pin "5") (pinfunction "VREF_5") (pintype "bidirectional"))
    )
    (net (code "131") (name "unconnected-(U4-PB4-Pad10)") (class "Default")
      (node (ref "U4") (pin "10") (pinfunction "PB4_10") (pintype "bidirectional"))
    )
    (net (code "132") (name "unconnected-(U4-PB5-Pad9)") (class "Default")
      (node (ref "U4") (pin "9") (pinfunction "PB5_9") (pintype "bidirectional"))
    )
    (net (code "133") (name "~{CAN_CS}") (class "Default")
      (node (ref "U1") (pin "16") (pinfunction "CS_16") (pintype "input"))
      (node (ref "U4") (pin "18") (pinfunction "PC3_18") (pintype "bidirectional"))
    )
    (net (code "134") (name "~{OUT_CS}") (class "Default")
      (node (ref "JP1") (pin "11") (pinfunction "11_11") (pintype "passive"))
      (node (ref "SPI") (pin "6") (pinfunction "6_6") (pintype "bidirectional"))
      (node (ref "U4") (pin "5") (pinfunction "PA4_5") (pintype "bidirectional"))
    )
  )
)
